# upvol.net
KiCad netlist of a schematic drawn in EAGLE
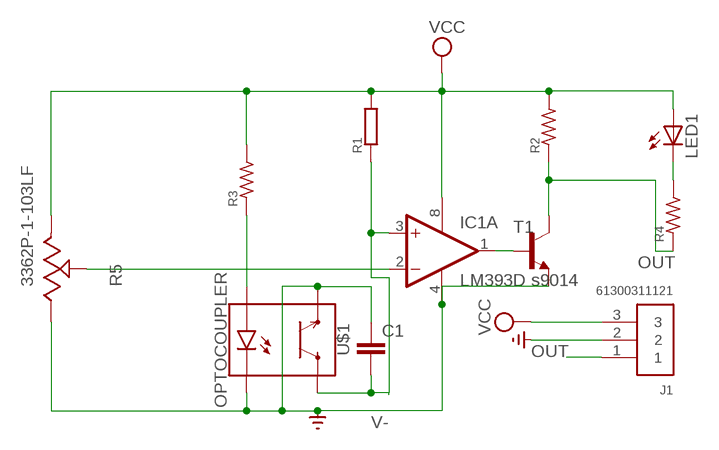
[diagram p0: schematic, sheet 1]

(export (version "E")
  (design (tool "Eeschema 10.0.6"))
  (components
    (comp (ref "C1")
      (value "C2.5/2")
      (footprint "eagle-import:C2.5-2")
      (libsource (lib "eagle-import") (part "C2.5/2"))
    )
    (comp (ref "IC1")
      (value "LM393D")
      (footprint "eagle-import:SO08")
      (libsource (lib "eagle-import") (part "LM393D"))
    )
    (comp (ref "J1")
      (value "61300311121")
      (footprint "eagle-import:61300311121")
      (fields
        (field (name "DIGI_KEY_PART_NUMBER") "732-5316-ND")
        (field (name "MANUFACTURER") "Wurth Electronics Inc.")
        (field (name "CREATED_BY") "PCBLayout.com")
      )
      (libsource (lib "eagle-import") (part "61300311121"))
    )
    (comp (ref "LED1")
      (value "LED3MM")
      (footprint "eagle-import:LED3MM")
      (libsource (lib "eagle-import") (part "LED3MM"))
    )
    (comp (ref "R1")
      (value "10K")
      (footprint "eagle-import:0204V")
      (libsource (lib "eagle-import") (part "R-EU_0204/2V"))
    )
    (comp (ref "R2")
      (value "10K")
      (footprint "eagle-import:RC-MASTER-SMD_R0603MP")
      (libsource (lib "eagle-import") (part "RC-MASTER-SMD_R_0603MP"))
    )
    (comp (ref "R3")
      (value "4.7k")
      (footprint "eagle-import:RC-MASTER-SMD_R0603MP")
      (libsource (lib "eagle-import") (part "RC-MASTER-SMD_R_0603MP"))
    )
    (comp (ref "R4")
      (value "10K")
      (footprint "eagle-import:RC-MASTER-SMD_R0603MP")
      (libsource (lib "eagle-import") (part "RC-MASTER-SMD_R_0603MP"))
    )
    (comp (ref "R5")
      (value "3362P-1-103LF")
      (footprint "eagle-import:3362P-1-103LF")
      (fields (field (name "MANUFACTURER") "Bourns Inc.") (field (name "CREATED_PN") "PCBLayout.com"))
      (libsource (lib "eagle-import") (part "3362P-1-103LF"))
    )
    (comp (ref "T1")
      (value "s9014")
      (footprint "eagle-import:SOT23-EBC")
      (libsource (lib "eagle-import") (part "-NPN-SOT23-EBC"))
    )
    (comp (ref "U$1")
      (value "OPTOCOUPLER")
      (footprint "eagle-import:OPTOCOUPLER")
      (libsource (lib "eagle-import") (part "OPTOCOUPLER"))
    )
  )
  (nets
    (net (code "1") (name "/OUT") (class "Default")
      (node (ref "J1") (pin "1") (pinfunction "1_1") (pintype "passive"))
      (node (ref "R2") (pin "1") (pinfunction "1_1") (pintype "passive"))
      (node (ref "R4") (pin "1") (pinfunction "1_1") (pintype "passive"))
      (node (ref "T1") (pin "C") (pinfunction "C_C") (pintype "passive"))
    )
    (net (code "2") (name "Net-(IC1A-+IN)") (class "Default")
      (node (ref "C1") (pin "2") (pinfunction "2_2") (pintype "passive"))
      (node (ref "IC1") (pin "3") (pinfunction "+IN_3") (pintype "input"))
      (node (ref "R1") (pin "1") (pinfunction "1_1") (pintype "passive"))
      (node (ref "U$1") (pin "C") (pinfunction "C_C") (pintype "passive"))
    )
    (net (code "3") (name "Net-(IC1A--IN)") (class "Default")
      (node (ref "IC1") (pin "2") (pinfunction "-IN_2") (pintype "input"))
      (node (ref "R5") (pin "2") (pinfunction "2_2") (pintype "passive"))
    )
    (net (code "4") (name "Net-(IC1A-OUT)") (class "Default")
      (node (ref "IC1") (pin "1") (pinfunction "OUT_1") (pintype "output"))
      (node (ref "T1") (pin "B") (pinfunction "B_B") (pintype "passive"))
    )
    (net (code "5") (name "Net-(LED1-C)") (class "Default")
      (node (ref "LED1") (pin "K") (pinfunction "C_K") (pintype "passive"))
      (node (ref "R4") (pin "2") (pinfunction "2_2") (pintype "passive"))
    )
    (net (code "6") (name "Net-(R3-Pad1)") (class "Default")
      (node (ref "R3") (pin "1") (pinfunction "1_1") (pintype "passive"))
      (node (ref "U$1") (pin "A") (pinfunction "A_A") (pintype "passive"))
    )
    (net (code "7") (name "SUPPLY_BRASTAN_GND_") (class "Default")
      (node (ref "C1") (pin "1") (pinfunction "1_1") (pintype "passive"))
      (node (ref "IC1") (pin "4") (pinfunction "V-_4") (pintype "power_in"))
      (node (ref "J1") (pin "2") (pinfunction "2_2") (pintype "passive"))
      (node (ref "R5") (pin "3") (pinfunction "3_3") (pintype "passive"))
      (node (ref "T1") (pin "E") (pinfunction "E_E") (pintype "passive"))
      (node (ref "U$1") (pin "E") (pinfunction "E_E") (pintype "passive"))
      (node (ref "U$1") (pin "K") (pinfunction "K_K") (pintype "passive"))
    )
    (net (code "8") (name "VCC") (class "Default")
      (node (ref "IC1") (pin "8") (pinfunction "V+_8") (pintype "power_in"))
      (node (ref "J1") (pin "3") (pinfunction "3_3") (pintype "passive"))
      (node (ref "LED1") (pin "A") (pinfunction "A_A") (pintype "passive"))
      (node (ref "R1") (pin "2") (pinfunction "2_2") (pintype "passive"))
      (node (ref "R2") (pin "2") (pinfunction "2_2") (pintype "passive"))
      (node (ref "R3") (pin "2") (pinfunction "2_2") (pintype "passive"))
      (node (ref "R5") (pin "1") (pinfunction "1_1") (pintype "passive"))
    )
  )
)
